# CONTROL.net
KiCad netlist of a schematic drawn in EAGLE
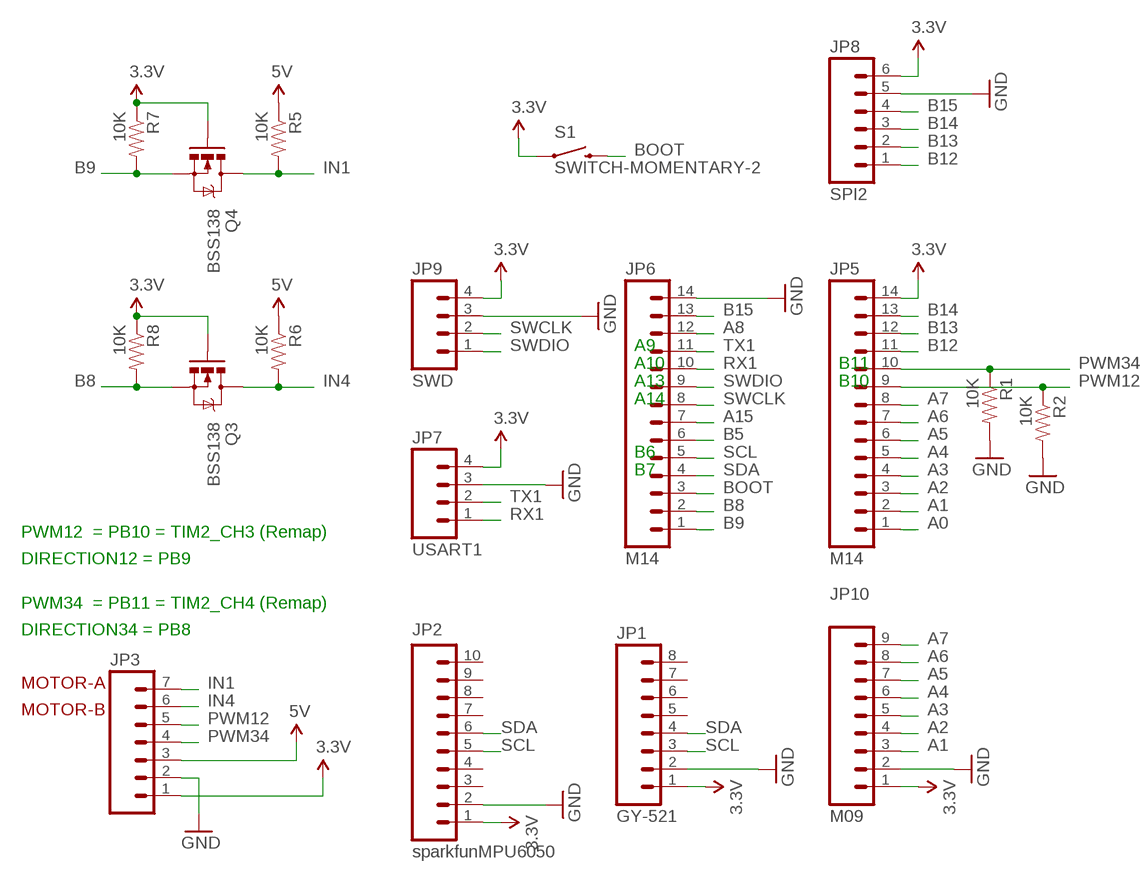
[diagram p0: schematic, sheet 1]

(export (version "E")
  (design (tool "Eeschema 10.0.6"))
  (components
    (comp (ref "JP1")
      (value "GY-521")
      (footprint "eagle-import:1X08")
      (libsource (lib "eagle-import") (part "M081X08"))
    )
    (comp (ref "JP2")
      (value "sparkfunMPU6050")
      (footprint "eagle-import:1X10")
      (libsource (lib "eagle-import") (part "M10{dblquote}"))
    )
    (comp (ref "JP3")
      (value "M07LONGPADS")
      (footprint "eagle-import:1X07_LONGPADS")
      (libsource (lib "eagle-import") (part "M07LONGPADS"))
    )
    (comp (ref "JP5")
      (value "M14")
      (footprint "eagle-import:1X14")
      (libsource (lib "eagle-import") (part "M14"))
    )
    (comp (ref "JP6")
      (value "M14")
      (footprint "eagle-import:1X14")
      (libsource (lib "eagle-import") (part "M14"))
    )
    (comp (ref "JP7")
      (value "USART1")
      (footprint "eagle-import:1X04")
      (libsource (lib "eagle-import") (part "M04PTH"))
    )
    (comp (ref "JP8")
      (value "SPI2")
      (footprint "eagle-import:1X06")
      (libsource (lib "eagle-import") (part "M06SIP"))
    )
    (comp (ref "JP9")
      (value "SWD")
      (footprint "eagle-import:1X04")
      (libsource (lib "eagle-import") (part "M04PTH"))
    )
    (comp (ref "JP10")
      (value "M09")
      (footprint "eagle-import:1X09")
      (libsource (lib "eagle-import") (part "M09"))
    )
    (comp (ref "Q3")
      (value "BSS138")
      (footprint "eagle-import:SOT23-3")
      (libsource (lib "eagle-import") (part "MOSFET-NCHANNELSMD"))
    )
    (comp (ref "Q4")
      (value "BSS138")
      (footprint "eagle-import:SOT23-3")
      (libsource (lib "eagle-import") (part "MOSFET-NCHANNELSMD"))
    )
    (comp (ref "R1")
      (value "10K")
      (footprint "eagle-import:0805")
      (libsource (lib "eagle-import") (part "RESISTOR0805-RES"))
    )
    (comp (ref "R2")
      (value "10K")
      (footprint "eagle-import:0805")
      (libsource (lib "eagle-import") (part "RESISTOR0805-RES"))
    )
    (comp (ref "R5")
      (value "10K")
      (footprint "eagle-import:0805")
      (libsource (lib "eagle-import") (part "RESISTOR0805-RES"))
    )
    (comp (ref "R6")
      (value "10K")
      (footprint "eagle-import:0805")
      (libsource (lib "eagle-import") (part "RESISTOR0805-RES"))
    )
    (comp (ref "R7")
      (value "10K")
      (footprint "eagle-import:0805")
      (libsource (lib "eagle-import") (part "RESISTOR0805-RES"))
    )
    (comp (ref "R8")
      (value "10K")
      (footprint "eagle-import:0805")
      (libsource (lib "eagle-import") (part "RESISTOR0805-RES"))
    )
    (comp (ref "S1")
      (value "SWITCH-MOMENTARY-2")
      (footprint "eagle-import:TACTILE_SWITCH_TALL")
      (libsource (lib "eagle-import") (part "SWITCH-MOMENTARY-2"))
    )
  )
  (nets
    (net (code "1") (name "/A0") (class "Default")
      (node (ref "JP5") (pin "1") (pinfunction "1_1") (pintype "passive"))
    )
    (net (code "2") (name "/A1") (class "Default")
      (node (ref "JP10") (pin "3") (pinfunction "3_3") (pintype "passive"))
      (node (ref "JP5") (pin "2") (pinfunction "2_2") (pintype "passive"))
    )
    (net (code "3") (name "/A2") (class "Default")
      (node (ref "JP10") (pin "4") (pinfunction "4_4") (pintype "passive"))
      (node (ref "JP5") (pin "3") (pinfunction "3_3") (pintype "passive"))
    )
    (net (code "4") (name "/A3") (class "Default")
      (node (ref "JP10") (pin "5") (pinfunction "5_5") (pintype "passive"))
      (node (ref "JP5") (pin "4") (pinfunction "4_4") (pintype "passive"))
    )
    (net (code "5") (name "/A4") (class "Default")
      (node (ref "JP10") (pin "6") (pinfunction "6_6") (pintype "passive"))
      (node (ref "JP5") (pin "5") (pinfunction "5_5") (pintype "passive"))
    )
    (net (code "6") (name "/A5") (class "Default")
      (node (ref "JP10") (pin "7") (pinfunction "7_7") (pintype "passive"))
      (node (ref "JP5") (pin "6") (pinfunction "6_6") (pintype "passive"))
    )
    (net (code "7") (name "/A6") (class "Default")
      (node (ref "JP10") (pin "8") (pinfunction "8_8") (pintype "passive"))
      (node (ref "JP5") (pin "7") (pinfunction "7_7") (pintype "passive"))
    )
    (net (code "8") (name "/A7") (class "Default")
      (node (ref "JP10") (pin "9") (pinfunction "9_9") (pintype "passive"))
      (node (ref "JP5") (pin "8") (pinfunction "8_8") (pintype "passive"))
    )
    (net (code "9") (name "/A8") (class "Default")
      (node (ref "JP6") (pin "12") (pinfunction "12_12") (pintype "passive"))
    )
    (net (code "10") (name "/A15") (class "Default")
      (node (ref "JP6") (pin "7") (pinfunction "7_7") (pintype "passive"))
    )
    (net (code "11") (name "/B5") (class "Default")
      (node (ref "JP6") (pin "6") (pinfunction "6_6") (pintype "passive"))
    )
    (net (code "12") (name "/B8") (class "Default")
      (node (ref "JP6") (pin "2") (pinfunction "2_2") (pintype "passive"))
      (node (ref "Q3") (pin "2") (pinfunction "S_2") (pintype "passive"))
      (node (ref "R8") (pin "2") (pinfunction "2_2") (pintype "passive"))
    )
    (net (code "13") (name "/B9") (class "Default")
      (node (ref "JP6") (pin "1") (pinfunction "1_1") (pintype "passive"))
      (node (ref "Q4") (pin "2") (pinfunction "S_2") (pintype "passive"))
      (node (ref "R7") (pin "2") (pinfunction "2_2") (pintype "passive"))
    )
    (net (code "14") (name "/B12") (class "Default")
      (node (ref "JP5") (pin "11") (pinfunction "11_11") (pintype "passive"))
      (node (ref "JP8") (pin "1") (pinfunction "1_1") (pintype "passive"))
    )
    (net (code "15") (name "/B13") (class "Default")
      (node (ref "JP5") (pin "12") (pinfunction "12_12") (pintype "passive"))
      (node (ref "JP8") (pin "2") (pinfunction "2_2") (pintype "passive"))
    )
    (net (code "16") (name "/B14") (class "Default")
      (node (ref "JP5") (pin "13") (pinfunction "13_13") (pintype "passive"))
      (node (ref "JP8") (pin "3") (pinfunction "3_3") (pintype "passive"))
    )
    (net (code "17") (name "/B15") (class "Default")
      (node (ref "JP6") (pin "13") (pinfunction "13_13") (pintype "passive"))
      (node (ref "JP8") (pin "4") (pinfunction "4_4") (pintype "passive"))
    )
    (net (code "18") (name "/BOOT") (class "Default")
      (node (ref "JP6") (pin "3") (pinfunction "3_3") (pintype "passive"))
      (node (ref "S1") (pin "B2") (pinfunction "2_B2") (pintype "passive"))
    )
    (net (code "19") (name "/IN1") (class "Default")
      (node (ref "JP3") (pin "7") (pinfunction "7_7") (pintype "passive"))
      (node (ref "Q4") (pin "3") (pinfunction "D_3") (pintype "passive"))
      (node (ref "R5") (pin "2") (pinfunction "2_2") (pintype "passive"))
    )
    (net (code "20") (name "/IN4") (class "Default")
      (node (ref "JP3") (pin "6") (pinfunction "6_6") (pintype "passive"))
      (node (ref "Q3") (pin "3") (pinfunction "D_3") (pintype "passive"))
      (node (ref "R6") (pin "2") (pinfunction "2_2") (pintype "passive"))
    )
    (net (code "21") (name "/PWM12") (class "Default")
      (node (ref "JP3") (pin "5") (pinfunction "5_5") (pintype "passive"))
      (node (ref "JP5") (pin "9") (pinfunction "9_9") (pintype "passive"))
      (node (ref "R2") (pin "1") (pinfunction "1_1") (pintype "passive"))
    )
    (net (code "22") (name "/PWM34") (class "Default")
      (node (ref "JP3") (pin "4") (pinfunction "4_4") (pintype "passive"))
      (node (ref "JP5") (pin "10") (pinfunction "10_10") (pintype "passive"))
      (node (ref "R1") (pin "1") (pinfunction "1_1") (pintype "passive"))
    )
    (net (code "23") (name "/RX1") (class "Default")
      (node (ref "JP6") (pin "10") (pinfunction "10_10") (pintype "passive"))
      (node (ref "JP7") (pin "1") (pinfunction "1_1") (pintype "passive"))
    )
    (net (code "24") (name "/SCL") (class "Default")
      (node (ref "JP1") (pin "3") (pinfunction "3_3") (pintype "passive"))
      (node (ref "JP2") (pin "5") (pinfunction "5_5") (pintype "passive"))
      (node (ref "JP6") (pin "5") (pinfunction "5_5") (pintype "passive"))
    )
    (net (code "25") (name "/SDA") (class "Default")
      (node (ref "JP1") (pin "4") (pinfunction "4_4") (pintype "passive"))
      (node (ref "JP2") (pin "6") (pinfunction "6_6") (pintype "passive"))
      (node (ref "JP6") (pin "4") (pinfunction "4_4") (pintype "passive"))
    )
    (net (code "26") (name "/SWCLK") (class "Default")
      (node (ref "JP6") (pin "8") (pinfunction "8_8") (pintype "passive"))
      (node (ref "JP9") (pin "2") (pinfunction "2_2") (pintype "passive"))
    )
    (net (code "27") (name "/SWDIO") (class "Default")
      (node (ref "JP6") (pin "9") (pinfunction "9_9") (pintype "passive"))
      (node (ref "JP9") (pin "1") (pinfunction "1_1") (pintype "passive"))
    )
    (net (code "28") (name "/TX1") (class "Default")
      (node (ref "JP6") (pin "11") (pinfunction "11_11") (pintype "passive"))
      (node (ref "JP7") (pin "2") (pinfunction "2_2") (pintype "passive"))
    )
    (net (code "29") (name "3.3V") (class "Default")
      (node (ref "JP1") (pin "1") (pinfunction "1_1") (pintype "passive"))
      (node (ref "JP10") (pin "1") (pinfunction "1_1") (pintype "passive"))
      (node (ref "JP2") (pin "1") (pinfunction "1_1") (pintype "passive"))
      (node (ref "JP3") (pin "1") (pinfunction "1_1") (pintype "passive"))
      (node (ref "JP5") (pin "14") (pinfunction "14_14") (pintype "passive"))
      (node (ref "JP7") (pin "4") (pinfunction "4_4") (pintype "passive"))
      (node (ref "JP8") (pin "6") (pinfunction "6_6") (pintype "passive"))
      (node (ref "JP9") (pin "4") (pinfunction "4_4") (pintype "passive"))
      (node (ref "Q3") (pin "1") (pinfunction "G_1") (pintype "passive"))
      (node (ref "Q4") (pin "1") (pinfunction "G_1") (pintype "passive"))
      (node (ref "R7") (pin "1") (pinfunction "1_1") (pintype "passive"))
      (node (ref "R8") (pin "1") (pinfunction "1_1") (pintype "passive"))
      (node (ref "S1") (pin "A2") (pinfunction "1_A2") (pintype "passive"))
    )
    (net (code "30") (name "5V") (class "Default")
      (node (ref "JP3") (pin "3") (pinfunction "3_3") (pintype "passive"))
      (node (ref "R5") (pin "1") (pinfunction "1_1") (pintype "passive"))
      (node (ref "R6") (pin "1") (pinfunction "1_1") (pintype "passive"))
    )
    (net (code "31") (name "GND") (class "Default")
      (node (ref "JP1") (pin "2") (pinfunction "2_2") (pintype "passive"))
      (node (ref "JP10") (pin "2") (pinfunction "2_2") (pintype "passive"))
      (node (ref "JP2") (pin "2") (pinfunction "2_2") (pintype "passive"))
      (node (ref "JP3") (pin "2") (pinfunction "2_2") (pintype "passive"))
      (node (ref "JP6") (pin "14") (pinfunction "14_14") (pintype "passive"))
      (node (ref "JP7") (pin "3") (pinfunction "3_3") (pintype "passive"))
      (node (ref "JP8") (pin "5") (pinfunction "5_5") (pintype "passive"))
      (node (ref "JP9") (pin "3") (pinfunction "3_3") (pintype "passive"))
      (node (ref "R1") (pin "2") (pinfunction "2_2") (pintype "passive"))
      (node (ref "R2") (pin "2") (pinfunction "2_2") (pintype "passive"))
    )
    (net (code "32") (name "unconnected-(JP1-Pad5)") (class "Default")
      (node (ref "JP1") (pin "5") (pinfunction "5_5") (pintype "passive"))
    )
    (net (code "33") (name "unconnected-(JP1-Pad6)") (class "Default")
      (node (ref "JP1") (pin "6") (pinfunction "6_6") (pintype "passive"))
    )
    (net (code "34") (name "unconnected-(JP1-Pad7)") (class "Default")
      (node (ref "JP1") (pin "7") (pinfunction "7_7") (pintype "passive"))
    )
    (net (code "35") (name "unconnected-(JP1-Pad8)") (class "Default")
      (node (ref "JP1") (pin "8") (pinfunction "8_8") (pintype "passive"))
    )
    (net (code "36") (name "unconnected-(JP2-Pad3)") (class "Default")
      (node (ref "JP2") (pin "3") (pinfunction "3_3") (pintype "passive"))
    )
    (net (code "37") (name "unconnected-(JP2-Pad4)") (class "Default")
      (node (ref "JP2") (pin "4") (pinfunction "4_4") (pintype "passive"))
    )
    (net (code "38") (name "unconnected-(JP2-Pad7)") (class "Default")
      (node (ref "JP2") (pin "7") (pinfunction "7_7") (pintype "passive"))
    )
    (net (code "39") (name "unconnected-(JP2-Pad8)") (class "Default")
      (node (ref "JP2") (pin "8") (pinfunction "8_8") (pintype "passive"))
    )
    (net (code "40") (name "unconnected-(JP2-Pad9)") (class "Default")
      (node (ref "JP2") (pin "9") (pinfunction "9_9") (pintype "passive"))
    )
    (net (code "41") (name "unconnected-(JP2-Pad10)") (class "Default")
      (node (ref "JP2") (pin "10") (pinfunction "10_10") (pintype "passive"))
    )
  )
)
